# 5VPrimary.net
KiCad netlist of a schematic drawn in Altium Designer
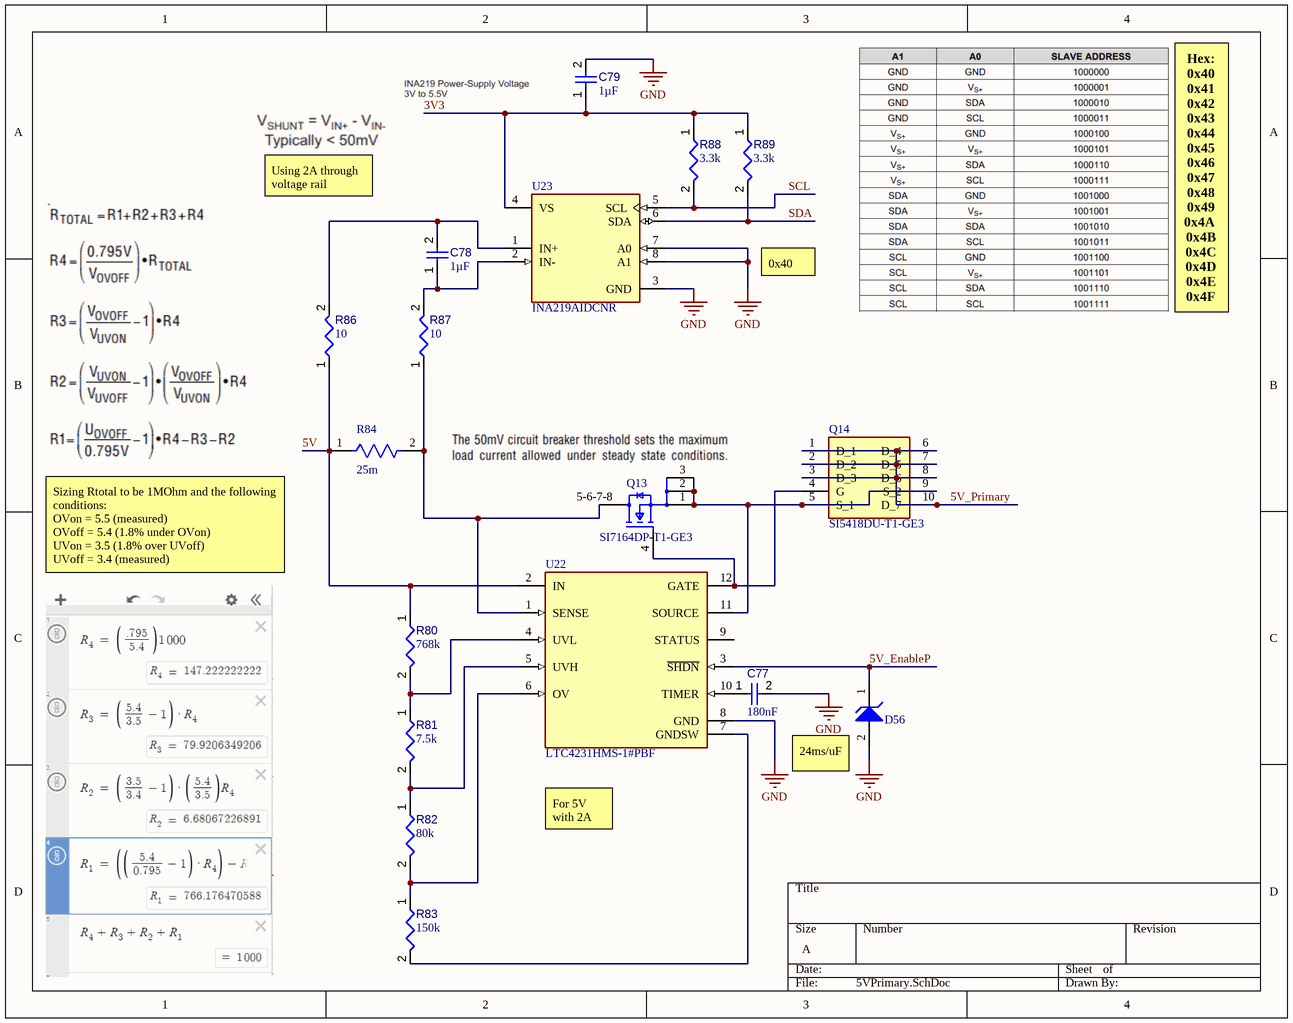
[diagram p0: 5VPrimary.SchDoc]

(export (version "E")
  (design (tool "Eeschema 10.0.6"))
  (components
    (comp (ref "C77")
      (value "180nF")
      (footprint "FP-C0805C-DN-IPC_A")
      (fields (field (name "Comment") "C0805C184K5RACTU"))
      (libsource (lib "UGA SSRL Hardware Team") (part "CAP-NP-2"))
    )
    (comp (ref "C78")
      (value "1µF")
      (footprint "CAPC1608X90X40LL10T20")
      (description "Chip Capacitor, 1 uF, +/- 10%, 25 V, 0603 (1608 Metric)")
      (fields (field (name "TOLERANCE") "10%") (field (name "Comment") "Capacitor 1 uF +/- 10% 25 V 0603"))
      (libsource (lib "UGA SSRL Hardware Team") (part "CAP-NP-2"))
    )
    (comp (ref "C79")
      (value "1µF")
      (footprint "CAPC1608X90X35ML15T15")
      (description "Chip Capacitor, 1 uF, +/- 10%, 16 V, 0603 (1608 Metric)")
      (fields (field (name "TOLERANCE") "10%") (field (name "Comment") "Capacitor 1uF +/- 10% 16V 0603"))
      (libsource (lib "UGA SSRL Hardware Team") (part "CAP-NP-2"))
    )
    (comp (ref "D56")
      (value "MM3Z3V6T1G")
      (footprint "ONSC-SOD-323-2-477-02_V")
      (description "Zener Voltage Regulator, 300 mW, 2-Pin SOD-323, Pb-Free, Tape and Reel")
      (fields (field (name "MANUFACTURER") "On Semiconductor"))
      (libsource (lib "Altium Content Vault") (part "ONSC-K1A2-2"))
    )
    (comp (ref "Q13")
      (value "SI7164DP-T1-GE3")
      (footprint "Vishay_S17-0173-SINGLE_MFG")
      (libsource (lib "UGA SSRL Hardware Team") (part "SI7164DP-T1-GE3"))
    )
    (comp (ref "Q14")
      (value "SI5418DU-T1-GE3")
      (footprint "SI5418DU-T1-GE3-Footprint-1")
      (libsource (lib "UGA SSRL Hardware Team") (part "SI5418DU-T1-GE3-Symbol-1"))
    )
    (comp (ref "R80")
      (value "768k")
      (footprint "RESC0402(1005)_L")
      (description "768K 0.063W 1% 0402 (1005 Metric)  SMD")
      (fields (field (name "TOLERANCE") "1%") (field (name "POWER") "63mW"))
      (libsource (lib "UGA SSRL Hardware Team") (part "768KR2F"))
    )
    (comp (ref "R81")
      (value "7.5k")
      (footprint "FP-CRCW1206-e3-IPC_A")
      (fields
        (field (name "TOLERANCE") "1%")
        (field (name "POWER") "250mW")
        (field (name "Comment") "CRCW12067K50FKEA")
      )
      (libsource (lib "UGA SSRL Hardware Team") (part "RES-2"))
    )
    (comp (ref "R82")
      (value "80k")
      (footprint "FP-PTN0603-IPC_B")
      (description "Fixed Resistor, Thin Film, 0.15W, 80000ohm, 75V, 0.1% +/-Tol, 25ppm/Cel, Surface Mount, 0603")
      (fields (field (name "POWER") "150mW") (field (name "TOLERANCE") "0.1%"))
      (libsource (lib "UGA SSRL Hardware Team") (part "RES-2"))
    )
    (comp (ref "R83")
      (value "150k")
      (footprint "FP-RT1206-IPC_C")
      (description "Fixed Resistor, Thin Film, 0.25W, 150000ohm, 200V, 1% +/-Tol, 50ppm/Cel, Surface Mount, 1206")
      (fields (field (name "TOLERANCE") "1%") (field (name "POWER") "250mW"))
      (libsource (lib "UGA SSRL Hardware Team") (part "RES-2"))
    )
    (comp (ref "R84")
      (value "CSR1206FK25L0")
      (footprint "FP-CSR1206-IPC_C")
      (description "General Purpose Thick Film Chip Resistor, 1206, 25mΩ, 1%, 0.5W")
      (fields (field (name "RESISTANCE") "25m") (field (name "TOLERANCE") "1%"))
      (libsource (lib "Altium Content Vault") (part "1029c3af85768c4190bb7ad29bc67b5"))
    )
    (comp (ref "R86")
      (value "10")
      (footprint "RESC0402(1005)_L")
      (description "Chip Resistor, 10 Ohms, +/-1 %, 63 mW, -55 to 155 degC, 0402")
      (fields (field (name "TOLERANCE") "1%") (field (name "POWER") "63mW"))
      (libsource (lib "UGA SSRL Hardware Team") (part "RES-2"))
    )
    (comp (ref "R87")
      (value "10")
      (footprint "RESC0402(1005)_L")
      (description "Chip Resistor, 10 Ohms, +/-1 %, 63 mW, -55 to 155 degC, 0402")
      (fields (field (name "TOLERANCE") "1%") (field (name "POWER") "63mW"))
      (libsource (lib "UGA SSRL Hardware Team") (part "RES-2"))
    )
    (comp (ref "R88")
      (value "3.3k")
      (footprint "FP-CRCW1210-e3-IPC_C")
      (fields
        (field (name "TOLERANCE") "5%")
        (field (name "POWER") "500mW")
        (field (name "Comment") "CRCW12103K30JNEA")
      )
      (libsource (lib "UGA SSRL Hardware Team") (part "RES-2"))
    )
    (comp (ref "R89")
      (value "3.3k")
      (footprint "FP-CRCW1210-e3-IPC_C")
      (fields
        (field (name "TOLERANCE") "5%")
        (field (name "POWER") "500mW")
        (field (name "Comment") "CRCW12103K30JNEA")
      )
      (libsource (lib "UGA SSRL Hardware Team") (part "RES-2"))
    )
    (comp (ref "U22")
      (value "LTC4231HMS-1#PBF")
      (footprint "FP-MS-12-05-08-1668-MFG")
      (description "IC HOT SWAP CTRLR GP 12MSOP")
      (libsource (lib "Altium Content Vault") (part "22a006f8750c3b6cd4295fbd2c2f62c"))
    )
    (comp (ref "U23")
      (value "INA219AIDCNR")
      (footprint "FP-DCN0008A-IPC_A")
      (description "Power Supply Support Circuit, Fixed, 2 Channel, 2V, PDSO8")
      (libsource (lib "UGA SSRL Hardware Team") (part "e16934b8ef90d0e345b266f0ae9cd81"))
    )
  )
  (nets
    (net (code "1") (name "/3V3") (class "Default")
      (node (ref "C79") (pin "1") (pinfunction "1_1") (pintype "passive"))
      (node (ref "R88") (pin "1") (pinfunction "1_1") (pintype "passive"))
      (node (ref "R89") (pin "1") (pinfunction "1_1") (pintype "passive"))
      (node (ref "U23") (pin "4") (pinfunction "VS_4") (pintype "power_in"))
    )
    (net (code "2") (name "/5V") (class "Default")
      (node (ref "R80") (pin "1") (pinfunction "1_1") (pintype "passive"))
      (node (ref "R84") (pin "1") (pinfunction "1_1") (pintype "passive"))
      (node (ref "R86") (pin "1") (pinfunction "1_1") (pintype "passive"))
      (node (ref "U22") (pin "2") (pinfunction "IN_2") (pintype "power_in"))
    )
    (net (code "3") (name "/5V_EnableP") (class "Default")
      (node (ref "D56") (pin "1") (pinfunction "K_1") (pintype "passive"))
      (node (ref "U22") (pin "3") (pinfunction "~{SHDN}_3") (pintype "input"))
    )
    (net (code "4") (name "/5V_Primary") (class "Default")
      (node (ref "Q14") (pin "1") (pinfunction "D_1_1") (pintype "passive"))
      (node (ref "Q14") (pin "10") (pinfunction "D_7_10") (pintype "passive"))
      (node (ref "Q14") (pin "2") (pinfunction "D_2_2") (pintype "passive"))
      (node (ref "Q14") (pin "3") (pinfunction "D_3_3") (pintype "passive"))
      (node (ref "Q14") (pin "6") (pinfunction "D_4_6") (pintype "passive"))
      (node (ref "Q14") (pin "7") (pinfunction "D_5_7") (pintype "passive"))
      (node (ref "Q14") (pin "8") (pinfunction "D_6_8") (pintype "passive"))
    )
    (net (code "5") (name "/SCL") (class "Default")
      (node (ref "R88") (pin "2") (pinfunction "2_2") (pintype "passive"))
      (node (ref "U23") (pin "5") (pinfunction "SCL_5") (pintype "input"))
    )
    (net (code "6") (name "/SDA") (class "Default")
      (node (ref "R89") (pin "2") (pinfunction "2_2") (pintype "passive"))
      (node (ref "U23") (pin "6") (pinfunction "SDA_6") (pintype "bidirectional"))
    )
    (net (code "7") (name "GND") (class "Default")
      (node (ref "C77") (pin "2") (pinfunction "2_2") (pintype "passive"))
      (node (ref "C79") (pin "2") (pinfunction "2_2") (pintype "passive"))
      (node (ref "D56") (pin "2") (pinfunction "A_2") (pintype "passive"))
      (node (ref "U22") (pin "8") (pinfunction "GND_8") (pintype "power_in"))
      (node (ref "U23") (pin "3") (pinfunction "GND_3") (pintype "power_in"))
      (node (ref "U23") (pin "7") (pinfunction "A0_7") (pintype "input"))
      (node (ref "U23") (pin "8") (pinfunction "A1_8") (pintype "input"))
    )
    (net (code "8") (name "Net-(Q13-D)") (class "Default")
      (node (ref "Q13") (pin "5-6-7-8") (pinfunction "D_5-6-7-8") (pintype "passive"))
      (node (ref "R84") (pin "2") (pinfunction "2_2") (pintype "passive"))
      (node (ref "R87") (pin "1") (pinfunction "1_1") (pintype "passive"))
      (node (ref "U22") (pin "1") (pinfunction "SENSE_1") (pintype "input"))
    )
    (net (code "9") (name "Net-(Q13-G)") (class "Default")
      (node (ref "Q13") (pin "4") (pinfunction "G_4") (pintype "passive"))
      (node (ref "Q14") (pin "4") (pinfunction "G_4") (pintype "passive"))
      (node (ref "U22") (pin "12") (pinfunction "GATE_12") (pintype "passive"))
    )
    (net (code "10") (name "Net-(Q14-S_1)") (class "Default")
      (node (ref "Q13") (pin "1") (pinfunction "S_1") (pintype "passive"))
      (node (ref "Q13") (pin "2") (pinfunction "S_2") (pintype "passive"))
      (node (ref "Q13") (pin "3") (pinfunction "S_3") (pintype "passive"))
      (node (ref "Q14") (pin "5") (pinfunction "S_1_5") (pintype "passive"))
      (node (ref "Q14") (pin "9") (pinfunction "S_2_9") (pintype "passive"))
      (node (ref "U22") (pin "11") (pinfunction "SOURCE_11") (pintype "passive"))
    )
    (net (code "11") (name "Net-(U22-GNDSW)") (class "Default")
      (node (ref "R83") (pin "2") (pinfunction "2_2") (pintype "passive"))
      (node (ref "U22") (pin "7") (pinfunction "GNDSW_7") (pintype "power_in"))
    )
    (net (code "12") (name "Net-(U22-OV)") (class "Default")
      (node (ref "R82") (pin "2") (pinfunction "2_2") (pintype "passive"))
      (node (ref "R83") (pin "1") (pinfunction "1_1") (pintype "passive"))
      (node (ref "U22") (pin "6") (pinfunction "OV_6") (pintype "input"))
    )
    (net (code "13") (name "Net-(U22-TIMER)") (class "Default")
      (node (ref "C77") (pin "1") (pinfunction "1_1") (pintype "passive"))
      (node (ref "U22") (pin "10") (pinfunction "TIMER_10") (pintype "input"))
    )
    (net (code "14") (name "Net-(U22-UVH)") (class "Default")
      (node (ref "R81") (pin "2") (pinfunction "2_2") (pintype "passive"))
      (node (ref "R82") (pin "1") (pinfunction "1_1") (pintype "passive"))
      (node (ref "U22") (pin "5") (pinfunction "UVH_5") (pintype "input"))
    )
    (net (code "15") (name "Net-(U22-UVL)") (class "Default")
      (node (ref "R80") (pin "2") (pinfunction "2_2") (pintype "passive"))
      (node (ref "R81") (pin "1") (pinfunction "1_1") (pintype "passive"))
      (node (ref "U22") (pin "4") (pinfunction "UVL_4") (pintype "input"))
    )
    (net (code "16") (name "Net-(U23-IN+)") (class "Default")
      (node (ref "C78") (pin "2") (pinfunction "2_2") (pintype "passive"))
      (node (ref "R86") (pin "2") (pinfunction "2_2") (pintype "passive"))
      (node (ref "U23") (pin "1") (pinfunction "IN+_1") (pintype "passive"))
    )
    (net (code "17") (name "Net-(U23-IN-)") (class "Default")
      (node (ref "C78") (pin "1") (pinfunction "1_1") (pintype "passive"))
      (node (ref "R87") (pin "2") (pinfunction "2_2") (pintype "passive"))
      (node (ref "U23") (pin "2") (pinfunction "IN-_2") (pintype "input"))
    )
    (net (code "18") (name "unconnected-(U22-STATUS-Pad9)") (class "Default")
      (node (ref "U22") (pin "9") (pinfunction "STATUS_9") (pintype "open_collector"))
    )
  )
)
